# bio_dnt_main.net
KiCad netlist of a schematic drawn in Altium Designer
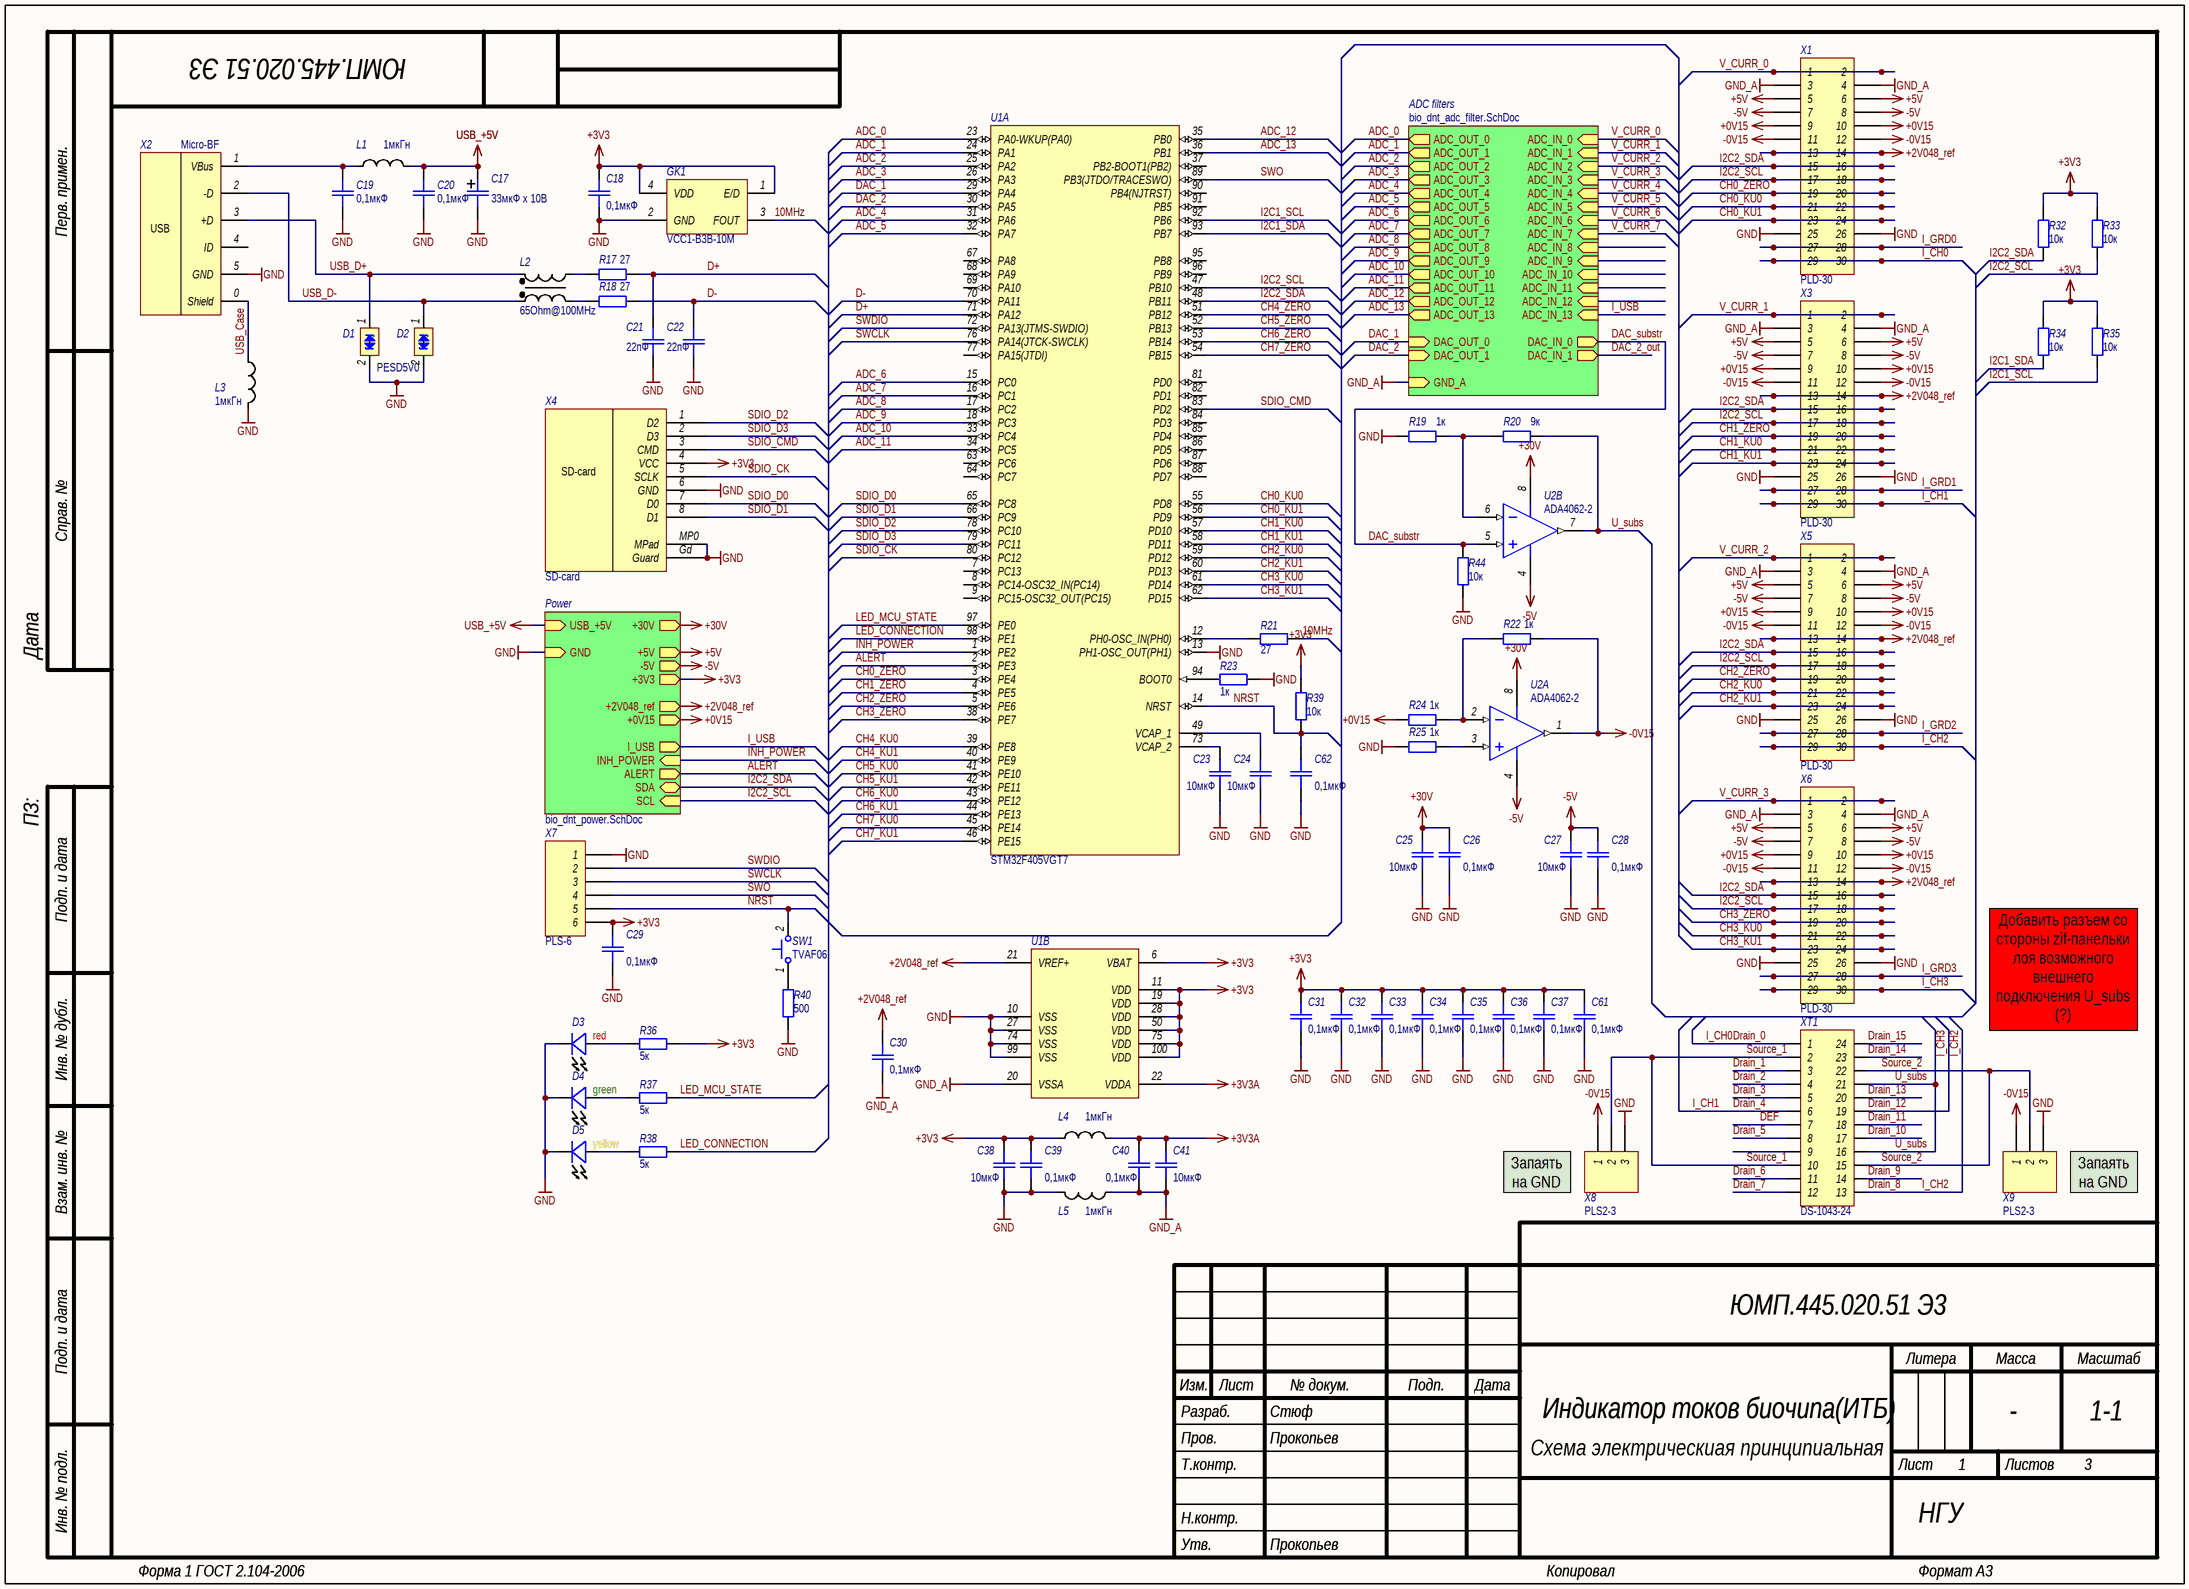
[diagram p0: bio_dnt_main.SchDoc]

(export (version "E")
  (design (tool "Eeschema 10.0.6"))
  (components
    (comp (ref "C17")
      (value "33мкФ х 10В")
      (footprint "C_SMD_size_C")
      (description "Поляризованный конеднсатор для поверхностного монтажа")
      (libsource (lib "my_passive") (part "C_pol_smd"))
    )
    (comp (ref "C18")
      (value "0,1мкФ")
      (footprint "CR-0805")
      (description "Конденсатор для поверхностного монтажа")
      (libsource (lib "my_passive") (part "C_smd"))
    )
    (comp (ref "C19")
      (value "0,1мкФ")
      (footprint "CR-0805")
      (description "Конденсатор для поверхностного монтажа")
      (libsource (lib "my_passive") (part "C_smd"))
    )
    (comp (ref "C20")
      (value "0,1мкФ")
      (footprint "CR-0805")
      (description "Конденсатор для поверхностного монтажа")
      (libsource (lib "my_passive") (part "C_smd"))
    )
    (comp (ref "C21")
      (value "22пФ")
      (footprint "CR-0805")
      (description "Конденсатор для поверхностного монтажа")
      (libsource (lib "my_passive") (part "C_smd"))
    )
    (comp (ref "C22")
      (value "22пФ")
      (footprint "CR-0805")
      (description "Конденсатор для поверхностного монтажа")
      (libsource (lib "my_passive") (part "C_smd"))
    )
    (comp (ref "C23")
      (value "10мкФ")
      (footprint "CR-0805")
      (description "Конденсатор для поверхностного монтажа")
      (libsource (lib "my_passive") (part "C_smd"))
    )
    (comp (ref "C24")
      (value "10мкФ")
      (footprint "CR-0805")
      (description "Конденсатор для поверхностного монтажа")
      (libsource (lib "my_passive") (part "C_smd"))
    )
    (comp (ref "C25")
      (value "10мкФ")
      (footprint "CR-0805")
      (description "Конденсатор для поверхностного монтажа")
      (libsource (lib "my_passive") (part "C_smd"))
    )
    (comp (ref "C26")
      (value "0,1мкФ")
      (footprint "CR-0805")
      (description "Конденсатор для поверхностного монтажа")
      (libsource (lib "my_passive") (part "C_smd"))
    )
    (comp (ref "C27")
      (value "10мкФ")
      (footprint "CR-0805")
      (description "Конденсатор для поверхностного монтажа")
      (libsource (lib "my_passive") (part "C_smd"))
    )
    (comp (ref "C28")
      (value "0,1мкФ")
      (footprint "CR-0805")
      (description "Конденсатор для поверхностного монтажа")
      (libsource (lib "my_passive") (part "C_smd"))
    )
    (comp (ref "C29")
      (value "0,1мкФ")
      (footprint "CR-0805")
      (description "Конденсатор для поверхностного монтажа")
      (libsource (lib "my_passive") (part "C_smd"))
    )
    (comp (ref "C30")
      (value "0,1мкФ")
      (footprint "CR-0805")
      (description "Конденсатор для поверхностного монтажа")
      (libsource (lib "my_passive") (part "C_smd"))
    )
    (comp (ref "C31")
      (value "0,1мкФ")
      (footprint "CR-0805")
      (description "Конденсатор для поверхностного монтажа")
      (libsource (lib "my_passive") (part "C_smd"))
    )
    (comp (ref "C32")
      (value "0,1мкФ")
      (footprint "CR-0805")
      (description "Конденсатор для поверхностного монтажа")
      (libsource (lib "my_passive") (part "C_smd"))
    )
    (comp (ref "C33")
      (value "0,1мкФ")
      (footprint "CR-0805")
      (description "Конденсатор для поверхностного монтажа")
      (libsource (lib "my_passive") (part "C_smd"))
    )
    (comp (ref "C34")
      (value "0,1мкФ")
      (footprint "CR-0805")
      (description "Конденсатор для поверхностного монтажа")
      (libsource (lib "my_passive") (part "C_smd"))
    )
    (comp (ref "C35")
      (value "0,1мкФ")
      (footprint "CR-0805")
      (description "Конденсатор для поверхностного монтажа")
      (libsource (lib "my_passive") (part "C_smd"))
    )
    (comp (ref "C36")
      (value "0,1мкФ")
      (footprint "CR-0805")
      (description "Конденсатор для поверхностного монтажа")
      (libsource (lib "my_passive") (part "C_smd"))
    )
    (comp (ref "C37")
      (value "0,1мкФ")
      (footprint "CR-0805")
      (description "Конденсатор для поверхностного монтажа")
      (libsource (lib "my_passive") (part "C_smd"))
    )
    (comp (ref "C38")
      (value "10мкФ")
      (footprint "CR-0805")
      (description "Конденсатор для поверхностного монтажа")
      (libsource (lib "my_passive") (part "C_smd"))
    )
    (comp (ref "C39")
      (value "0,1мкФ")
      (footprint "CR-0805")
      (description "Конденсатор для поверхностного монтажа")
      (libsource (lib "my_passive") (part "C_smd"))
    )
    (comp (ref "C40")
      (value "0,1мкФ")
      (footprint "CR-0805")
      (description "Конденсатор для поверхностного монтажа")
      (libsource (lib "my_passive") (part "C_smd"))
    )
    (comp (ref "C41")
      (value "10мкФ")
      (footprint "CR-0805")
      (description "Конденсатор для поверхностного монтажа")
      (libsource (lib "my_passive") (part "C_smd"))
    )
    (comp (ref "C61")
      (value "0,1мкФ")
      (footprint "CR-0805")
      (description "Конденсатор для поверхностного монтажа")
      (libsource (lib "my_passive") (part "C_smd"))
    )
    (comp (ref "C62")
      (value "0,1мкФ")
      (footprint "CR-0805")
      (description "Конденсатор для поверхностного монтажа")
      (libsource (lib "my_passive") (part "C_smd"))
    )
    (comp (ref "D1")
      (value "PESD5V0")
      (footprint "SOD-323")
      (description "Low capacitance bidirectional ESD protection diodes")
      (libsource (lib "my_semicond") (part "PESD5V0S"))
    )
    (comp (ref "D2")
      (value "PESD5V0")
      (footprint "SOD-323")
      (description "Low capacitance bidirectional ESD protection diodes")
      (libsource (lib "my_semicond") (part "PESD5V0S"))
    )
    (comp (ref "D3")
      (value "red")
      (footprint "LED-0805")
      (fields (field (name "Comment") "LED"))
      (libsource (lib "my_semicond") (part "LED"))
    )
    (comp (ref "D4")
      (value "green")
      (footprint "LED-0805")
      (fields (field (name "Comment") "LED"))
      (libsource (lib "my_semicond") (part "LED"))
    )
    (comp (ref "D5")
      (value "yellow")
      (footprint "LED-0805")
      (fields (field (name "Comment") "LED"))
      (libsource (lib "my_semicond") (part "LED"))
    )
    (comp (ref "GK1")
      (value "VCC1")
      (footprint "5x7 Crystall Oscillatior")
      (fields (field (name "НАИМЕНОВАНИЕ") "VCC1-B3B-10M"))
      (libsource (lib "my_integrated_circuit") (part "Crystall Oscillator"))
    )
    (comp (ref "L1")
      (value "1мкГн")
      (footprint "CR-1206")
      (description "Индуктивность для поверхностнгого монтажа")
      (libsource (lib "my_passive") (part "L_smd"))
    )
    (comp (ref "L2")
      (value "65Ohm@100MHz")
      (footprint "ACM2012")
      (description "USB common mode filter")
      (libsource (lib "my_passive") (part "ACM2012_USB_CM_FILTER"))
    )
    (comp (ref "L3")
      (value "1мкГн")
      (footprint "CR-1206-0805")
      (description "Индуктивность для поверхностнгого монтажа")
      (libsource (lib "my_passive") (part "L_smd"))
    )
    (comp (ref "L4")
      (value "1мкГн")
      (footprint "CR-1206-0805")
      (description "Индуктивность для поверхностнгого монтажа")
      (libsource (lib "my_passive") (part "L_smd"))
    )
    (comp (ref "L5")
      (value "1мкГн")
      (footprint "CR-1206-0805")
      (description "Индуктивность для поверхностнгого монтажа")
      (libsource (lib "my_passive") (part "L_smd"))
    )
    (comp (ref "R17")
      (value "27")
      (footprint "CR-0805")
      (description "Резистор для поверхностного монтажа")
      (libsource (lib "") (part "R_smd_1"))
    )
    (comp (ref "R18")
      (value "27")
      (footprint "CR-0805")
      (description "Резистор для поверхностного монтажа")
      (libsource (lib "") (part "R_smd_1"))
    )
    (comp (ref "R19")
      (value "1к")
      (footprint "CR-0805")
      (description "Резистор для поверхностного монтажа")
      (libsource (lib "") (part "R_smd_1"))
    )
    (comp (ref "R20")
      (value "9к")
      (footprint "CR-0805")
      (description "Резистор для поверхностного монтажа")
      (libsource (lib "") (part "R_smd_1"))
    )
    (comp (ref "R21")
      (value "27")
      (footprint "CR-0805")
      (description "Резистор для поверхностного монтажа")
      (libsource (lib "") (part "R_smd_2"))
    )
    (comp (ref "R22")
      (value "1к")
      (footprint "CR-0805")
      (description "Резистор для поверхностного монтажа")
      (libsource (lib "") (part "R_smd_1"))
    )
    (comp (ref "R23")
      (value "1к")
      (footprint "CR-0805")
      (description "Резистор для поверхностного монтажа")
      (libsource (lib "") (part "R_smd_1"))
    )
    (comp (ref "R24")
      (value "1к")
      (footprint "CR-0805")
      (description "Резистор для поверхностного монтажа")
      (libsource (lib "") (part "R_smd_1"))
    )
    (comp (ref "R25")
      (value "1к")
      (footprint "CR-0805")
      (description "Резистор для поверхностного монтажа")
      (libsource (lib "") (part "R_smd_1"))
    )
    (comp (ref "R32")
      (value "10к")
      (footprint "CR-0805")
      (description "Резистор для поверхностного монтажа")
      (libsource (lib "my_passive") (part "R_smd"))
    )
    (comp (ref "R33")
      (value "10к")
      (footprint "CR-0805")
      (description "Резистор для поверхностного монтажа")
      (libsource (lib "my_passive") (part "R_smd"))
    )
    (comp (ref "R34")
      (value "10к")
      (footprint "CR-0805")
      (description "Резистор для поверхностного монтажа")
      (libsource (lib "my_passive") (part "R_smd"))
    )
    (comp (ref "R35")
      (value "10к")
      (footprint "CR-0805")
      (description "Резистор для поверхностного монтажа")
      (libsource (lib "my_passive") (part "R_smd"))
    )
    (comp (ref "R36")
      (value "5к")
      (footprint "CR-0805")
      (description "Резистор для поверхностного монтажа")
      (libsource (lib "") (part "R_smd_1"))
    )
    (comp (ref "R37")
      (value "5к")
      (footprint "CR-0805")
      (description "Резистор для поверхностного монтажа")
      (libsource (lib "") (part "R_smd_1"))
    )
    (comp (ref "R38")
      (value "5к")
      (footprint "CR-0805")
      (description "Резистор для поверхностного монтажа")
      (libsource (lib "") (part "R_smd_1"))
    )
    (comp (ref "R39")
      (value "10к")
      (footprint "CR-0805")
      (description "Резистор для поверхностного монтажа")
      (libsource (lib "my_passive") (part "R_smd"))
    )
    (comp (ref "R40")
      (value "500")
      (footprint "CR-0805")
      (description "Резистор для поверхностного монтажа")
      (libsource (lib "") (part "R_smd_3"))
    )
    (comp (ref "R44")
      (value "10к")
      (footprint "CR-0805")
      (description "Резистор для поверхностного монтажа")
      (libsource (lib "my_passive") (part "R_smd"))
    )
    (comp (ref "SW1")
      (value "Push button")
      (footprint "TVAF06")
      (fields (field (name "НАИМЕНОВАНИЕ") "TVAF06"))
      (libsource (lib "my_passive") (part "Push_Button"))
    )
    (comp (ref "U1")
      (value "STM32F405VGT7")
      (footprint "LQFP100")
      (fields
        (field (name "MANUFACTURER") "STMicroelectronics")
        (field (name "НАИМЕНОВАНИЕ") "STM32F405VGT7")
      )
      (libsource (lib "") (part "STM32F405VGT_1"))
    )
    (comp (ref "U2")
      (value "ADA4062-2ARZ")
      (footprint "SOIC-8")
      (fields
        (field (name "GENERIC PART NUMBER") "ADA4062-2")
        (field (name "MANUFACTURER") "Analog Devices")
        (field (name "НАИМЕНОВАНИЕ") "ADA4062-2")
      )
      (libsource (lib "my_op_amplifier") (part "ADA4062-2"))
    )
    (comp (ref "X1")
      (value "HDR2X15")
      (footprint "HDR2X15")
      (description "Header, 15-Pin, Dual row")
      (fields (field (name "НАИМЕНОВАНИЕ") "PLD-30") (field (name "PUBLISHER") "Altium Limited"))
      (libsource (lib "my_connector") (part "HDR2X15"))
    )
    (comp (ref "X2")
      (value "mico-BF")
      (footprint "USB Micro-BF")
      (description "USB mico-BF")
      (fields (field (name "НАИМЕНОВАНИЕ") "Micro-BF"))
      (libsource (lib "my_connector") (part "MicroUSB"))
    )
    (comp (ref "X3")
      (value "HDR2X15")
      (footprint "HDR2X15")
      (description "Header, 15-Pin, Dual row")
      (fields (field (name "НАИМЕНОВАНИЕ") "PLD-30") (field (name "PUBLISHER") "Altium Limited"))
      (libsource (lib "my_connector") (part "HDR2X15"))
    )
    (comp (ref "X4")
      (value "SD-card")
      (footprint "SD-card holder")
      (description "SD-card holder")
      (fields (field (name "НАИМЕНОВАНИЕ") "SD-card"))
      (libsource (lib "my_connector") (part "SD-card holder"))
    )
    (comp (ref "X5")
      (value "HDR2X15")
      (footprint "HDR2X15")
      (description "Header, 15-Pin, Dual row")
      (fields (field (name "НАИМЕНОВАНИЕ") "PLD-30") (field (name "PUBLISHER") "Altium Limited"))
      (libsource (lib "my_connector") (part "HDR2X15"))
    )
    (comp (ref "X6")
      (value "HDR2X15")
      (footprint "HDR2X15")
      (description "Header, 15-Pin, Dual row")
      (fields (field (name "НАИМЕНОВАНИЕ") "PLD-30") (field (name "PUBLISHER") "Altium Limited"))
      (libsource (lib "my_connector") (part "HDR2X15"))
    )
    (comp (ref "X7")
      (value "Header 6")
      (footprint "HDR1X6")
      (description "Header, 6-Pin")
      (fields (field (name "НАИМЕНОВАНИЕ") "PLS-6") (field (name "PUBLISHER") "Altium Limited"))
      (libsource (lib "Miscellaneous Connectors") (part "Header 6"))
    )
    (comp (ref "X8")
      (value "MHDR1X3")
      (footprint "MHDR1X3")
      (description "Header, 3-Pin")
      (fields (field (name "НАИМЕНОВАНИЕ") "PLS2-3") (field (name "PUBLISHER") "Altium Limited"))
      (libsource (lib "my_connector") (part "MHDR1X3"))
    )
    (comp (ref "X9")
      (value "MHDR1X3")
      (footprint "MHDR1X3")
      (description "Header, 3-Pin")
      (fields (field (name "НАИМЕНОВАНИЕ") "PLS2-3") (field (name "PUBLISHER") "Altium Limited"))
      (libsource (lib "my_connector") (part "MHDR1X3"))
    )
    (comp (ref "XT1")
      (value "DS-1043-24")
      (footprint "DS-1043-24")
      (description "DIP-24 Zero Insertion Force (ZIF) socket")
      (fields (field (name "НАИМЕНОВАНИЕ") "DS-1043-24"))
      (libsource (lib "my_connector") (part "DS-1043-24"))
    )
  )
  (nets
    (net (code "1") (name "+0V15") (class "Default")
      (node (ref "R24") (pin "2") (pinfunction "2_2") (pintype "passive"))
      (node (ref "X1") (pin "10") (pinfunction "10_10") (pintype "passive"))
      (node (ref "X1") (pin "9") (pinfunction "9_9") (pintype "passive"))
      (node (ref "X3") (pin "10") (pinfunction "10_10") (pintype "passive"))
      (node (ref "X3") (pin "9") (pinfunction "9_9") (pintype "passive"))
      (node (ref "X5") (pin "10") (pinfunction "10_10") (pintype "passive"))
      (node (ref "X5") (pin "9") (pinfunction "9_9") (pintype "passive"))
      (node (ref "X6") (pin "10") (pinfunction "10_10") (pintype "passive"))
      (node (ref "X6") (pin "9") (pinfunction "9_9") (pintype "passive"))
    )
    (net (code "2") (name "+2V048_ref") (class "Default")
      (node (ref "C30") (pin "2") (pinfunction "2_2") (pintype "passive"))
      (node (ref "U1") (pin "21") (pinfunction "VREF+_21") (pintype "power_in"))
      (node (ref "X1") (pin "13") (pinfunction "13_13") (pintype "passive"))
      (node (ref "X1") (pin "14") (pinfunction "14_14") (pintype "passive"))
      (node (ref "X3") (pin "13") (pinfunction "13_13") (pintype "passive"))
      (node (ref "X3") (pin "14") (pinfunction "14_14") (pintype "passive"))
      (node (ref "X5") (pin "13") (pinfunction "13_13") (pintype "passive"))
      (node (ref "X5") (pin "14") (pinfunction "14_14") (pintype "passive"))
      (node (ref "X6") (pin "13") (pinfunction "13_13") (pintype "passive"))
      (node (ref "X6") (pin "14") (pinfunction "14_14") (pintype "passive"))
    )
    (net (code "3") (name "+3V3") (class "Default")
      (node (ref "C18") (pin "2") (pinfunction "2_2") (pintype "passive"))
      (node (ref "C29") (pin "2") (pinfunction "2_2") (pintype "passive"))
      (node (ref "C31") (pin "2") (pinfunction "2_2") (pintype "passive"))
      (node (ref "C32") (pin "2") (pinfunction "2_2") (pintype "passive"))
      (node (ref "C33") (pin "2") (pinfunction "2_2") (pintype "passive"))
      (node (ref "C34") (pin "2") (pinfunction "2_2") (pintype "passive"))
      (node (ref "C35") (pin "2") (pinfunction "2_2") (pintype "passive"))
      (node (ref "C36") (pin "2") (pinfunction "2_2") (pintype "passive"))
      (node (ref "C37") (pin "2") (pinfunction "2_2") (pintype "passive"))
      (node (ref "C38") (pin "2") (pinfunction "2_2") (pintype "passive"))
      (node (ref "C39") (pin "2") (pinfunction "2_2") (pintype "passive"))
      (node (ref "C61") (pin "2") (pinfunction "2_2") (pintype "passive"))
      (node (ref "GK1") (pin "1") (pinfunction "E/D_1") (pintype "passive"))
      (node (ref "GK1") (pin "4") (pinfunction "VDD_4") (pintype "passive"))
      (node (ref "L4") (pin "1") (pinfunction "1_1") (pintype "passive"))
      (node (ref "R32") (pin "1") (pinfunction "1_1") (pintype "passive"))
      (node (ref "R33") (pin "1") (pinfunction "1_1") (pintype "passive"))
      (node (ref "R34") (pin "1") (pinfunction "1_1") (pintype "passive"))
      (node (ref "R35") (pin "1") (pinfunction "1_1") (pintype "passive"))
      (node (ref "R36") (pin "1") (pinfunction "1_1") (pintype "passive"))
      (node (ref "R39") (pin "1") (pinfunction "1_1") (pintype "passive"))
      (node (ref "U1") (pin "100") (pinfunction "VDD_100") (pintype "power_in"))
      (node (ref "U1") (pin "11") (pinfunction "VDD_11") (pintype "power_in"))
      (node (ref "U1") (pin "19") (pinfunction "VDD_19") (pintype "power_in"))
      (node (ref "U1") (pin "28") (pinfunction "VDD_28") (pintype "power_in"))
      (node (ref "U1") (pin "50") (pinfunction "VDD_50") (pintype "power_in"))
      (node (ref "U1") (pin "6") (pinfunction "VBAT_6") (pintype "power_in"))
      (node (ref "U1") (pin "75") (pinfunction "VDD_75") (pintype "power_in"))
      (node (ref "X4") (pin "4") (pinfunction "VCC_4") (pintype "passive"))
      (node (ref "X7") (pin "6") (pinfunction "6_6") (pintype "passive"))
    )
    (net (code "4") (name "+3V3A") (class "Default")
      (node (ref "C40") (pin "2") (pinfunction "2_2") (pintype "passive"))
      (node (ref "C41") (pin "2") (pinfunction "2_2") (pintype "passive"))
      (node (ref "L4") (pin "2") (pinfunction "2_2") (pintype "passive"))
      (node (ref "U1") (pin "22") (pinfunction "VDDA_22") (pintype "power_in"))
    )
    (net (code "5") (name "+5V") (class "Default")
      (node (ref "X1") (pin "5") (pinfunction "5_5") (pintype "passive"))
      (node (ref "X1") (pin "6") (pinfunction "6_6") (pintype "passive"))
      (node (ref "X3") (pin "5") (pinfunction "5_5") (pintype "passive"))
      (node (ref "X3") (pin "6") (pinfunction "6_6") (pintype "passive"))
      (node (ref "X5") (pin "5") (pinfunction "5_5") (pintype "passive"))
      (node (ref "X5") (pin "6") (pinfunction "6_6") (pintype "passive"))
      (node (ref "X6") (pin "5") (pinfunction "5_5") (pintype "passive"))
      (node (ref "X6") (pin "6") (pinfunction "6_6") (pintype "passive"))
    )
    (net (code "6") (name "+30V") (class "Default")
      (node (ref "C25") (pin "2") (pinfunction "2_2") (pintype "passive"))
      (node (ref "C26") (pin "2") (pinfunction "2_2") (pintype "passive"))
      (node (ref "U2") (pin "8") (pinfunction "+V_8") (pintype "power_in"))
    )
    (net (code "7") (name "-0V15") (class "Default")
      (node (ref "R22") (pin "1") (pinfunction "1_1") (pintype "passive"))
      (node (ref "U2") (pin "1") (pinfunction "OUT_A_1") (pintype "output"))
      (node (ref "X1") (pin "11") (pinfunction "11_11") (pintype "passive"))
      (node (ref "X1") (pin "12") (pinfunction "12_12") (pintype "passive"))
      (node (ref "X3") (pin "11") (pinfunction "11_11") (pintype "passive"))
      (node (ref "X3") (pin "12") (pinfunction "12_12") (pintype "passive"))
      (node (ref "X5") (pin "11") (pinfunction "11_11") (pintype "passive"))
      (node (ref "X5") (pin "12") (pinfunction "12_12") (pintype "passive"))
      (node (ref "X6") (pin "11") (pinfunction "11_11") (pintype "passive"))
      (node (ref "X6") (pin "12") (pinfunction "12_12") (pintype "passive"))
      (node (ref "X8") (pin "1") (pinfunction "1_1") (pintype "passive"))
      (node (ref "X9") (pin "1") (pinfunction "1_1") (pintype "passive"))
    )
    (net (code "8") (name "-5V") (class "Default")
      (node (ref "C27") (pin "2") (pinfunction "2_2") (pintype "passive"))
      (node (ref "C28") (pin "2") (pinfunction "2_2") (pintype "passive"))
      (node (ref "U2") (pin "4") (pinfunction "-V_4") (pintype "power_in"))
      (node (ref "X1") (pin "7") (pinfunction "7_7") (pintype "passive"))
      (node (ref "X1") (pin "8") (pinfunction "8_8") (pintype "passive"))
      (node (ref "X3") (pin "7") (pinfunction "7_7") (pintype "passive"))
      (node (ref "X3") (pin "8") (pinfunction "8_8") (pintype "passive"))
      (node (ref "X5") (pin "7") (pinfunction "7_7") (pintype "passive"))
      (node (ref "X5") (pin "8") (pinfunction "8_8") (pintype "passive"))
      (node (ref "X6") (pin "7") (pinfunction "7_7") (pintype "passive"))
      (node (ref "X6") (pin "8") (pinfunction "8_8") (pintype "passive"))
    )
    (net (code "9") (name "/10MHz") (class "Default")
      (node (ref "GK1") (pin "3") (pinfunction "FOUT_3") (pintype "passive"))
      (node (ref "R21") (pin "2") (pinfunction "2_2") (pintype "passive"))
    )
    (net (code "10") (name "/ADC_0") (class "Default")
      (node (ref "U1") (pin "23") (pinfunction "PA0-WKUP(PA0)_23") (pintype "bidirectional"))
    )
    (net (code "11") (name "/ADC_1") (class "Default")
      (node (ref "U1") (pin "24") (pinfunction "PA1_24") (pintype "bidirectional"))
    )
    (net (code "12") (name "/ADC_2") (class "Default")
      (node (ref "U1") (pin "25") (pinfunction "PA2_25") (pintype "bidirectional"))
    )
    (net (code "13") (name "/ADC_3") (class "Default")
      (node (ref "U1") (pin "26") (pinfunction "PA3_26") (pintype "bidirectional"))
    )
    (net (code "14") (name "/ADC_4") (class "Default")
      (node (ref "U1") (pin "31") (pinfunction "PA6_31") (pintype "bidirectional"))
    )
    (net (code "15") (name "/ADC_5") (class "Default")
      (node (ref "U1") (pin "32") (pinfunction "PA7_32") (pintype "bidirectional"))
    )
    (net (code "16") (name "/ADC_6") (class "Default")
      (node (ref "U1") (pin "15") (pinfunction "PC0_15") (pintype "bidirectional"))
    )
    (net (code "17") (name "/ADC_7") (class "Default")
      (node (ref "U1") (pin "16") (pinfunction "PC1_16") (pintype "bidirectional"))
    )
    (net (code "18") (name "/ADC_8") (class "Default")
      (node (ref "U1") (pin "17") (pinfunction "PC2_17") (pintype "bidirectional"))
    )
    (net (code "19") (name "/ADC_9") (class "Default")
      (node (ref "U1") (pin "18") (pinfunction "PC3_18") (pintype "bidirectional"))
    )
    (net (code "20") (name "/ADC_10") (class "Default")
      (node (ref "U1") (pin "33") (pinfunction "PC4_33") (pintype "bidirectional"))
    )
    (net (code "21") (name "/ADC_11") (class "Default")
      (node (ref "U1") (pin "34") (pinfunction "PC5_34") (pintype "bidirectional"))
    )
    (net (code "22") (name "/ADC_12") (class "Default")
      (node (ref "U1") (pin "35") (pinfunction "PB0_35") (pintype "bidirectional"))
    )
    (net (code "23") (name "/ADC_13") (class "Default")
      (node (ref "U1") (pin "36") (pinfunction "PB1_36") (pintype "bidirectional"))
    )
    (net (code "29") (name "/ALERT") (class "Default")
      (node (ref "U1") (pin "2") (pinfunction "PE3_2") (pintype "bidirectional"))
    )
    (net (code "30") (name "/CH0_KU0") (class "Default")
      (node (ref "U1") (pin "55") (pinfunction "PD8_55") (pintype "bidirectional"))
      (node (ref "X1") (pin "21") (pinfunction "21_21") (pintype "passive"))
      (node (ref "X1") (pin "22") (pinfunction "22_22") (pintype "passive"))
    )
    (net (code "31") (name "/CH0_KU1") (class "Default")
      (node (ref "U1") (pin "56") (pinfunction "PD9_56") (pintype "bidirectional"))
      (node (ref "X1") (pin "23") (pinfunction "23_23") (pintype "passive"))
      (node (ref "X1") (pin "24") (pinfunction "24_24") (pintype "passive"))
    )
    (net (code "32") (name "/CH0_ZERO") (class "Default")
      (node (ref "U1") (pin "3") (pinfunction "PE4_3") (pintype "bidirectional"))
      (node (ref "X1") (pin "19") (pinfunction "19_19") (pintype "passive"))
      (node (ref "X1") (pin "20") (pinfunction "20_20") (pintype "passive"))
    )
    (net (code "33") (name "/CH1_KU0") (class "Default")
      (node (ref "U1") (pin "57") (pinfunction "PD10_57") (pintype "bidirectional"))
      (node (ref "X3") (pin "21") (pinfunction "21_21") (pintype "passive"))
      (node (ref "X3") (pin "22") (pinfunction "22_22") (pintype "passive"))
    )
    (net (code "34") (name "/CH1_KU1") (class "Default")
      (node (ref "U1") (pin "58") (pinfunction "PD11_58") (pintype "bidirectional"))
      (node (ref "X3") (pin "23") (pinfunction "23_23") (pintype "passive"))
      (node (ref "X3") (pin "24") (pinfunction "24_24") (pintype "passive"))
    )
    (net (code "35") (name "/CH1_ZERO") (class "Default")
      (node (ref "U1") (pin "4") (pinfunction "PE5_4") (pintype "bidirectional"))
      (node (ref "X3") (pin "19") (pinfunction "19_19") (pintype "passive"))
      (node (ref "X3") (pin "20") (pinfunction "20_20") (pintype "passive"))
    )
    (net (code "36") (name "/CH2_KU0") (class "Default")
      (node (ref "U1") (pin "59") (pinfunction "PD12_59") (pintype "bidirectional"))
      (node (ref "X5") (pin "21") (pinfunction "21_21") (pintype "passive"))
      (node (ref "X5") (pin "22") (pinfunction "22_22") (pintype "passive"))
    )
    (net (code "37") (name "/CH2_KU1") (class "Default")
      (node (ref "U1") (pin "60") (pinfunction "PD13_60") (pintype "bidirectional"))
      (node (ref "X5") (pin "23") (pinfunction "23_23") (pintype "passive"))
      (node (ref "X5") (pin "24") (pinfunction "24_24") (pintype "passive"))
    )
    (net (code "38") (name "/CH2_ZERO") (class "Default")
      (node (ref "U1") (pin "5") (pinfunction "PE6_5") (pintype "bidirectional"))
      (node (ref "X5") (pin "19") (pinfunction "19_19") (pintype "passive"))
      (node (ref "X5") (pin "20") (pinfunction "20_20") (pintype "passive"))
    )
    (net (code "39") (name "/CH3_KU0") (class "Default")
      (node (ref "U1") (pin "61") (pinfunction "PD14_61") (pintype "bidirectional"))
      (node (ref "X6") (pin "21") (pinfunction "21_21") (pintype "passive"))
      (node (ref "X6") (pin "22") (pinfunction "22_22") (pintype "passive"))
    )
    (net (code "40") (name "/CH3_KU1") (class "Default")
      (node (ref "U1") (pin "62") (pinfunction "PD15_62") (pintype "bidirectional"))
      (node (ref "X6") (pin "23") (pinfunction "23_23") (pintype "passive"))
      (node (ref "X6") (pin "24") (pinfunction "24_24") (pintype "passive"))
    )
    (net (code "41") (name "/CH3_ZERO") (class "Default")
      (node (ref "U1") (pin "38") (pinfunction "PE7_38") (pintype "bidirectional"))
      (node (ref "X6") (pin "19") (pinfunction "19_19") (pintype "passive"))
      (node (ref "X6") (pin "20") (pinfunction "20_20") (pintype "passive"))
    )
    (net (code "42") (name "/CH4_KU0") (class "Default")
      (node (ref "U1") (pin "39") (pinfunction "PE8_39") (pintype "bidirectional"))
    )
    (net (code "43") (name "/CH4_KU1") (class "Default")
      (node (ref "U1") (pin "40") (pinfunction "PE9_40") (pintype "bidirectional"))
    )
    (net (code "44") (name "/CH4_ZERO") (class "Default")
      (node (ref "U1") (pin "51") (pinfunction "PB12_51") (pintype "bidirectional"))
    )
    (net (code "45") (name "/CH5_KU0") (class "Default")
      (node (ref "U1") (pin "41") (pinfunction "PE10_41") (pintype "bidirectional"))
    )
    (net (code "46") (name "/CH5_KU1") (class "Default")
      (node (ref "U1") (pin "42") (pinfunction "PE11_42") (pintype "bidirectional"))
    )
    (net (code "47") (name "/CH5_ZERO") (class "Default")
      (node (ref "U1") (pin "52") (pinfunction "PB13_52") (pintype "bidirectional"))
    )
    (net (code "48") (name "/CH6_KU0") (class "Default")
      (node (ref "U1") (pin "43") (pinfunction "PE12_43") (pintype "bidirectional"))
    )
    (net (code "49") (name "/CH6_KU1") (class "Default")
      (node (ref "U1") (pin "44") (pinfunction "PE13_44") (pintype "bidirectional"))
    )
    (net (code "50") (name "/CH6_ZERO") (class "Default")
      (node (ref "U1") (pin "53") (pinfunction "PB14_53") (pintype "bidirectional"))
    )
    (net (code "51") (name "/CH7_KU0") (class "Default")
      (node (ref "U1") (pin "45") (pinfunction "PE14_45") (pintype "bidirectional"))
    )
    (net (code "52") (name "/CH7_KU1") (class "Default")
      (node (ref "U1") (pin "46") (pinfunction "PE15_46") (pintype "bidirectional"))
    )
    (net (code "53") (name "/CH7_ZERO") (class "Default")
      (node (ref "U1") (pin "54") (pinfunction "PB15_54") (pintype "bidirectional"))
    )
    (net (code "54") (name "/D+") (class "Default")
      (node (ref "C21") (pin "2") (pinfunction "2_2") (pintype "passive"))
      (node (ref "R17") (pin "1") (pinfunction "1_1") (pintype "passive"))
      (node (ref "U1") (pin "71") (pinfunction "PA12_71") (pintype "bidirectional"))
    )
    (net (code "55") (name "/D-") (class "Default")
      (node (ref "C22") (pin "2") (pinfunction "2_2") (pintype "passive"))
      (node (ref "R18") (pin "1") (pinfunction "1_1") (pintype "passive"))
      (node (ref "U1") (pin "70") (pinfunction "PA11_70") (pintype "bidirectional"))
    )
    (net (code "56") (name "/DAC_1") (class "Default")
      (node (ref "U1") (pin "29") (pinfunction "PA4_29") (pintype "bidirectional"))
    )
    (net (code "57") (name "/DAC_2") (class "Default")
      (node (ref "U1") (pin "30") (pinfunction "PA5_30") (pintype "bidirectional"))
    )
    (net (code "59") (name "/DAC_substr") (class "Default")
      (node (ref "R44") (pin "1") (pinfunction "1_1") (pintype "passive"))
      (node (ref "U2") (pin "5") (pinfunction "+IN_B_5") (pintype "input"))
    )
    (net (code "60") (name "/DEF") (class "Default")
      (node (ref "XT1") (pin "7") (pinfunction "7_7") (pintype "passive"))
    )
    (net (code "61") (name "/Drain_0") (class "Default")
      (node (ref "X1") (pin "29") (pinfunction "29_29") (pintype "passive"))
      (node (ref "X1") (pin "30") (pinfunction "30_30") (pintype "passive"))
      (node (ref "XT1") (pin "1") (pinfunction "1_1") (pintype "passive"))
    )
    (net (code "62") (name "/Drain_1") (class "Default")
      (node (ref "XT1") (pin "3") (pinfunction "3_3") (pintype "passive"))
    )
    (net (code "63") (name "/Drain_2") (class "Default")
      (node (ref "XT1") (pin "4") (pinfunction "4_4") (pintype "passive"))
    )
    (net (code "64") (name "/Drain_3") (class "Default")
      (node (ref "XT1") (pin "5") (pinfunction "5_5") (pintype "passive"))
    )
    (net (code "65") (name "/Drain_4") (class "Default")
      (node (ref "X3") (pin "29") (pinfunction "29_29") (pintype "passive"))
      (node (ref "X3") (pin "30") (pinfunction "30_30") (pintype "passive"))
      (node (ref "XT1") (pin "6") (pinfunction "6_6") (pintype "passive"))
    )
    (net (code "66") (name "/Drain_5") (class "Default")
      (node (ref "XT1") (pin "8") (pinfunction "8_8") (pintype "passive"))
    )
    (net (code "67") (name "/Drain_6") (class "Default")
      (node (ref "XT1") (pin "11") (pinfunction "11_11") (pintype "passive"))
    )
    (net (code "68") (name "/Drain_7") (class "Default")
      (node (ref "XT1") (pin "12") (pinfunction "12_12") (pintype "passive"))
    )
    (net (code "69") (name "/Drain_8") (class "Default")
      (node (ref "X5") (pin "29") (pinfunction "29_29") (pintype "passive"))
      (node (ref "X5") (pin "30") (pinfunction "30_30") (pintype "passive"))
      (node (ref "XT1") (pin "13") (pinfunction "13_13") (pintype "passive"))
    )
    (net (code "70") (name "/Drain_9") (class "Default")
      (node (ref "XT1") (pin "14") (pinfunction "14_14") (pintype "passive"))
    )
    (net (code "71") (name "/Drain_10") (class "Default")
      (node (ref "XT1") (pin "17") (pinfunction "17_17") (pintype "passive"))
    )
    (net (code "72") (name "/Drain_11") (class "Default")
      (node (ref "XT1") (pin "18") (pinfunction "18_18") (pintype "passive"))
    )
    (net (code "73") (name "/Drain_12") (class "Default")
      (node (ref "X6") (pin "29") (pinfunction "29_29") (pintype "passive"))
      (node (ref "X6") (pin "30") (pinfunction "30_30") (pintype "passive"))
      (node (ref "XT1") (pin "19") (pinfunction "19_19") (pintype "passive"))
    )
    (net (code "74") (name "/Drain_13") (class "Default")
      (node (ref "XT1") (pin "20") (pinfunction "20_20") (pintype "passive"))
    )
    (net (code "75") (name "/Drain_14") (class "Default")
      (node (ref "XT1") (pin "23") (pinfunction "23_23") (pintype "passive"))
    )
    (net (code "76") (name "/Drain_15") (class "Default")
      (node (ref "XT1") (pin "24") (pinfunction "24_24") (pintype "passive"))
    )
    (net (code "77") (name "/I2C1_SCL") (class "Default")
      (node (ref "R35") (pin "2") (pinfunction "2_2") (pintype "passive"))
      (node (ref "U1") (pin "92") (pinfunction "PB6_92") (pintype "bidirectional"))
    )
    (net (code "78") (name "/I2C1_SDA") (class "Default")
      (node (ref "R34") (pin "2") (pinfunction "2_2") (pintype "passive"))
      (node (ref "U1") (pin "93") (pinfunction "PB7_93") (pintype "bidirectional"))
    )
    (net (code "79") (name "/I2C2_SCL") (class "Default")
      (node (ref "R33") (pin "2") (pinfunction "2_2") (pintype "passive"))
      (node (ref "U1") (pin "47") (pinfunction "PB10_47") (pintype "bidirectional"))
      (node (ref "X1") (pin "17") (pinfunction "17_17") (pintype "passive"))
      (node (ref "X1") (pin "18") (pinfunction "18_18") (pintype "passive"))
      (node (ref "X3") (pin "17") (pinfunction "17_17") (pintype "passive"))
      (node (ref "X3") (pin "18") (pinfunction "18_18") (pintype "passive"))
      (node (ref "X5") (pin "17") (pinfunction "17_17") (pintype "passive"))
      (node (ref "X5") (pin "18") (pinfunction "18_18") (pintype "passive"))
      (node (ref "X6") (pin "17") (pinfunction "17_17") (pintype "passive"))
      (node (ref "X6") (pin "18") (pinfunction "18_18") (pintype "passive"))
    )
    (net (code "80") (name "/I2C2_SDA") (class "Default")
      (node (ref "R32") (pin "2") (pinfunction "2_2") (pintype "passive"))
      (node (ref "U1") (pin "48") (pinfunction "PB11_48") (pintype "bidirectional"))
      (node (ref "X1") (pin "15") (pinfunction "15_15") (pintype "passive"))
      (node (ref "X1") (pin "16") (pinfunction "16_16") (pintype "passive"))
      (node (ref "X3") (pin "15") (pinfunction "15_15") (pintype "passive"))
      (node (ref "X3") (pin "16") (pinfunction "16_16") (pintype "passive"))
      (node (ref "X5") (pin "15") (pinfunction "15_15") (pintype "passive"))
      (node (ref "X5") (pin "16") (pinfunction "16_16") (pintype "passive"))
      (node (ref "X6") (pin "15") (pinfunction "15_15") (pintype "passive"))
      (node (ref "X6") (pin "16") (pinfunction "16_16") (pintype "passive"))
    )
    (net (code "81") (name "/INH_POWER") (class "Default")
      (node (ref "U1") (pin "1") (pinfunction "PE2_1") (pintype "bidirectional"))
    )
    (net (code "82") (name "/I_GRD0") (class "Default")
      (node (ref "X1") (pin "27") (pinfunction "27_27") (pintype "passive"))
      (node (ref "X1") (pin "28") (pinfunction "28_28") (pintype "passive"))
    )
    (net (code "83") (name "/I_GRD1") (class "Default")
      (node (ref "X3") (pin "27") (pinfunction "27_27") (pintype "passive"))
      (node (ref "X3") (pin "28") (pinfunction "28_28") (pintype "passive"))
    )
    (net (code "84") (name "/I_GRD2") (class "Default")
      (node (ref "X5") (pin "27") (pinfunction "27_27") (pintype "passive"))
      (node (ref "X5") (pin "28") (pinfunction "28_28") (pintype "passive"))
    )
    (net (code "85") (name "/I_GRD3") (class "Default")
      (node (ref "X6") (pin "27") (pinfunction "27_27") (pintype "passive"))
      (node (ref "X6") (pin "28") (pinfunction "28_28") (pintype "passive"))
    )
    (net (code "87") (name "/LED_CONNECTION") (class "Default")
      (node (ref "R38") (pin "1") (pinfunction "1_1") (pintype "passive"))
      (node (ref "U1") (pin "98") (pinfunction "PE1_98") (pintype "bidirectional"))
    )
    (net (code "88") (name "/LED_MCU_STATE") (class "Default")
      (node (ref "R37") (pin "1") (pinfunction "1_1") (pintype "passive"))
      (node (ref "U1") (pin "97") (pinfunction "PE0_97") (pintype "bidirectional"))
    )
    (net (code "89") (name "/NRST") (class "Default")
      (node (ref "C62") (pin "2") (pinfunction "2_2") (pintype "passive"))
      (node (ref "R39") (pin "2") (pinfunction "2_2") (pintype "passive"))
      (node (ref "SW1") (pin "2") (pinfunction "2_2") (pintype "passive"))
      (node (ref "U1") (pin "14") (pinfunction "NRST_14") (pintype "bidirectional"))
      (node (ref "X7") (pin "5") (pinfunction "5_5") (pintype "passive"))
    )
    (net (code "90") (name "/SDIO_CK") (class "Default")
      (node (ref "U1") (pin "80") (pinfunction "PC12_80") (pintype "bidirectional"))
      (node (ref "X4") (pin "5") (pinfunction "SCLK_5") (pintype "passive"))
    )
    (net (code "91") (name "/SDIO_CMD") (class "Default")
      (node (ref "U1") (pin "83") (pinfunction "PD2_83") (pintype "bidirectional"))
      (node (ref "X4") (pin "3") (pinfunction "CMD_3") (pintype "passive"))
    )
    (net (code "92") (name "/SDIO_D0") (class "Default")
      (node (ref "U1") (pin "65") (pinfunction "PC8_65") (pintype "bidirectional"))
      (node (ref "X4") (pin "7") (pinfunction "D0_7") (pintype "passive"))
    )
    (net (code "93") (name "/SDIO_D1") (class "Default")
      (node (ref "U1") (pin "66") (pinfunction "PC9_66") (pintype "bidirectional"))
      (node (ref "X4") (pin "8") (pinfunction "D1_8") (pintype "passive"))
    )
    (net (code "94") (name "/SDIO_D2") (class "Default")
      (node (ref "U1") (pin "78") (pinfunction "PC10_78") (pintype "bidirectional"))
      (node (ref "X4") (pin "1") (pinfunction "D2_1") (pintype "passive"))
    )
    (net (code "95") (name "/SDIO_D3") (class "Default")
      (node (ref "U1") (pin "79") (pinfunction "PC11_79") (pintype "bidirectional"))
      (node (ref "X4") (pin "2") (pinfunction "D3_2") (pintype "passive"))
    )
    (net (code "96") (name "/SWCLK") (class "Default")
      (node (ref "U1") (pin "76") (pinfunction "PA14(JTCK-SWCLK)_76") (pintype "bidirectional"))
      (node (ref "X7") (pin "3") (pinfunction "3_3") (pintype "passive"))
    )
    (net (code "97") (name "/SWDIO") (class "Default")
      (node (ref "U1") (pin "72") (pinfunction "PA13(JTMS-SWDIO)_72") (pintype "bidirectional"))
      (node (ref "X7") (pin "2") (pinfunction "2_2") (pintype "passive"))
    )
    (net (code "98") (name "/SWO") (class "Default")
      (node (ref "U1") (pin "89") (pinfunction "PB3(JTDO/TRACESWO)_89") (pintype "bidirectional"))
      (node (ref "X7") (pin "4") (pinfunction "4_4") (pintype "passive"))
    )
    (net (code "99") (name "/Source_1") (class "Default")
      (node (ref "X8") (pin "2") (pinfunction "2_2") (pintype "passive"))
      (node (ref "XT1") (pin "10") (pinfunction "10_10") (pintype "passive"))
      (node (ref "XT1") (pin "2") (pinfunction "2_2") (pintype "passive"))
    )
    (net (code "100") (name "/Source_2") (class "Default")
      (node (ref "X9") (pin "2") (pinfunction "2_2") (pintype "passive"))
      (node (ref "XT1") (pin "15") (pinfunction "15_15") (pintype "passive"))
      (node (ref "XT1") (pin "22") (pinfunction "22_22") (pintype "passive"))
    )
    (net (code "101") (name "/USB_Case") (class "Default")
      (node (ref "L3") (pin "1") (pinfunction "1_1") (pintype "passive"))
      (node (ref "X2") (pin "0") (pinfunction "Shield_0") (pintype "passive"))
    )
    (net (code "102") (name "/USB_D+") (class "Default")
      (node (ref "D1") (pin "1") (pinfunction "cathode_1_1") (pintype "power_in"))
      (node (ref "L2") (pin "2") (pinfunction "2_2") (pintype "passive"))
      (node (ref "X2") (pin "3") (pinfunction "+D_3") (pintype "passive"))
    )
    (net (code "103") (name "/USB_D-") (class "Default")
      (node (ref "D2") (pin "1") (pinfunction "cathode_1_1") (pintype "power_in"))
      (node (ref "L2") (pin "1") (pinfunction "1_1") (pintype "passive"))
      (node (ref "X2") (pin "2") (pinfunction "-D_2") (pintype "passive"))
    )
    (net (code "104") (name "/U_subs") (class "Default")
      (node (ref "R20") (pin "1") (pinfunction "1_1") (pintype "passive"))
      (node (ref "U2") (pin "7") (pinfunction "OUT_B_7") (pintype "output"))
      (node (ref "XT1") (pin "16") (pinfunction "16_16") (pintype "passive"))
      (node (ref "XT1") (pin "21") (pinfunction "21_21") (pintype "passive"))
    )
    (net (code "105") (name "/V_CURR_0") (class "Default")
      (node (ref "X1") (pin "1") (pinfunction "1_1") (pintype "passive"))
      (node (ref "X1") (pin "2") (pinfunction "2_2") (pintype "passive"))
    )
    (net (code "106") (name "/V_CURR_1") (class "Default")
      (node (ref "X3") (pin "1") (pinfunction "1_1") (pintype "passive"))
      (node (ref "X3") (pin "2") (pinfunction "2_2") (pintype "passive"))
    )
    (net (code "107") (name "/V_CURR_2") (class "Default")
      (node (ref "X5") (pin "1") (pinfunction "1_1") (pintype "passive"))
      (node (ref "X5") (pin "2") (pinfunction "2_2") (pintype "passive"))
    )
    (net (code "108") (name "/V_CURR_3") (class "Default")
      (node (ref "X6") (pin "1") (pinfunction "1_1") (pintype "passive"))
      (node (ref "X6") (pin "2") (pinfunction "2_2") (pintype "passive"))
    )
    (net (code "113") (name "GND") (class "Default")
      (node (ref "C17") (pin "2") (pinfunction "2_2") (pintype "passive"))
      (node (ref "C18") (pin "1") (pinfunction "1_1") (pintype "passive"))
      (node (ref "C19") (pin "1") (pinfunction "1_1") (pintype "passive"))
      (node (ref "C20") (pin "1") (pinfunction "1_1") (pintype "passive"))
      (node (ref "C21") (pin "1") (pinfunction "1_1") (pintype "passive"))
      (node (ref "C22") (pin "1") (pinfunction "1_1") (pintype "passive"))
      (node (ref "C23") (pin "1") (pinfunction "1_1") (pintype "passive"))
      (node (ref "C24") (pin "1") (pinfunction "1_1") (pintype "passive"))
      (node (ref "C25") (pin "1") (pinfunction "1_1") (pintype "passive"))
      (node (ref "C26") (pin "1") (pinfunction "1_1") (pintype "passive"))
      (node (ref "C27") (pin "1") (pinfunction "1_1") (pintype "passive"))
      (node (ref "C28") (pin "1") (pinfunction "1_1") (pintype "passive"))
      (node (ref "C29") (pin "1") (pinfunction "1_1") (pintype "passive"))
      (node (ref "C31") (pin "1") (pinfunction "1_1") (pintype "passive"))
      (node (ref "C32") (pin "1") (pinfunction "1_1") (pintype "passive"))
      (node (ref "C33") (pin "1") (pinfunction "1_1") (pintype "passive"))
      (node (ref "C34") (pin "1") (pinfunction "1_1") (pintype "passive"))
      (node (ref "C35") (pin "1") (pinfunction "1_1") (pintype "passive"))
      (node (ref "C36") (pin "1") (pinfunction "1_1") (pintype "passive"))
      (node (ref "C37") (pin "1") (pinfunction "1_1") (pintype "passive"))
      (node (ref "C38") (pin "1") (pinfunction "1_1") (pintype "passive"))
      (node (ref "C39") (pin "1") (pinfunction "1_1") (pintype "passive"))
      (node (ref "C61") (pin "1") (pinfunction "1_1") (pintype "passive"))
      (node (ref "C62") (pin "1") (pinfunction "1_1") (pintype "passive"))
      (node (ref "D1") (pin "2") (pinfunction "cathode_2_2") (pintype "power_in"))
      (node (ref "D2") (pin "2") (pinfunction "cathode_2_2") (pintype "power_in"))
      (node (ref "D3") (pin "2") (pinfunction "K_2") (pintype "passive"))
      (node (ref "D4") (pin "2") (pinfunction "K_2") (pintype "passive"))
      (node (ref "D5") (pin "2") (pinfunction "K_2") (pintype "passive"))
      (node (ref "GK1") (pin "2") (pinfunction "GND_2") (pintype "passive"))
      (node (ref "L3") (pin "2") (pinfunction "2_2") (pintype "passive"))
      (node (ref "L5") (pin "2") (pinfunction "2_2") (pintype "passive"))
      (node (ref "R19") (pin "2") (pinfunction "2_2") (pintype "passive"))
      (node (ref "R23") (pin "1") (pinfunction "1_1") (pintype "passive"))
      (node (ref "R25") (pin "2") (pinfunction "2_2") (pintype "passive"))
      (node (ref "R40") (pin "1") (pinfunction "1_1") (pintype "passive"))
      (node (ref "R44") (pin "2") (pinfunction "2_2") (pintype "passive"))
      (node (ref "U1") (pin "10") (pinfunction "VSS_10") (pintype "power_in"))
      (node (ref "U1") (pin "13") (pinfunction "PH1-OSC_OUT(PH1)_13") (pintype "bidirectional"))
      (node (ref "U1") (pin "27") (pinfunction "VSS_27") (pintype "power_in"))
      (node (ref "U1") (pin "74") (pinfunction "VSS_74") (pintype "power_in"))
      (node (ref "U1") (pin "99") (pinfunction "VSS_99") (pintype "power_in"))
      (node (ref "X1") (pin "25") (pinfunction "25_25") (pintype "passive"))
      (node (ref "X1") (pin "26") (pinfunction "26_26") (pintype "passive"))
      (node (ref "X2") (pin "5") (pinfunction "GND_5") (pintype "passive"))
      (node (ref "X3") (pin "25") (pinfunction "25_25") (pintype "passive"))
      (node (ref "X3") (pin "26") (pinfunction "26_26") (pintype "passive"))
      (node (ref "X4") (pin "6") (pinfunction "GND_6") (pintype "passive"))
      (node (ref "X4") (pin "Gd") (pinfunction "Guard_Gd") (pintype "passive"))
      (node (ref "X4") (pin "MP0") (pinfunction "MPad_MP0") (pintype "passive"))
      (node (ref "X5") (pin "25") (pinfunction "25_25") (pintype "passive"))
      (node (ref "X5") (pin "26") (pinfunction "26_26") (pintype "passive"))
      (node (ref "X6") (pin "25") (pinfunction "25_25") (pintype "passive"))
      (node (ref "X6") (pin "26") (pinfunction "26_26") (pintype "passive"))
      (node (ref "X7") (pin "1") (pinfunction "1_1") (pintype "passive"))
      (node (ref "X8") (pin "3") (pinfunction "3_3") (pintype "passive"))
      (node (ref "X9") (pin "3") (pinfunction "3_3") (pintype "passive"))
    )
    (net (code "114") (name "GND_A") (class "Default")
      (node (ref "C30") (pin "1") (pinfunction "1_1") (pintype "passive"))
      (node (ref "C40") (pin "1") (pinfunction "1_1") (pintype "passive"))
      (node (ref "C41") (pin "1") (pinfunction "1_1") (pintype "passive"))
      (node (ref "L5") (pin "1") (pinfunction "1_1") (pintype "passive"))
      (node (ref "U1") (pin "20") (pinfunction "VSSA_20") (pintype "power_in"))
      (node (ref "X1") (pin "3") (pinfunction "3_3") (pintype "passive"))
      (node (ref "X1") (pin "4") (pinfunction "4_4") (pintype "passive"))
      (node (ref "X3") (pin "3") (pinfunction "3_3") (pintype "passive"))
      (node (ref "X3") (pin "4") (pinfunction "4_4") (pintype "passive"))
      (node (ref "X5") (pin "3") (pinfunction "3_3") (pintype "passive"))
      (node (ref "X5") (pin "4") (pinfunction "4_4") (pintype "passive"))
      (node (ref "X6") (pin "3") (pinfunction "3_3") (pintype "passive"))
      (node (ref "X6") (pin "4") (pinfunction "4_4") (pintype "passive"))
    )
    (net (code "115") (name "Net-(D3-A)") (class "Default")
      (node (ref "D3") (pin "1") (pinfunction "A_1") (pintype "passive"))
      (node (ref "R36") (pin "2") (pinfunction "2_2") (pintype "passive"))
    )
    (net (code "116") (name "Net-(D4-A)") (class "Default")
      (node (ref "D4") (pin "1") (pinfunction "A_1") (pintype "passive"))
      (node (ref "R37") (pin "2") (pinfunction "2_2") (pintype "passive"))
    )
    (net (code "117") (name "Net-(D5-A)") (class "Default")
      (node (ref "D5") (pin "1") (pinfunction "A_1") (pintype "passive"))
      (node (ref "R38") (pin "2") (pinfunction "2_2") (pintype "passive"))
    )
    (net (code "118") (name "Net-(L2-Pad3)") (class "Default")
      (node (ref "L2") (pin "3") (pinfunction "3_3") (pintype "passive"))
      (node (ref "R17") (pin "2") (pinfunction "2_2") (pintype "passive"))
    )
    (net (code "119") (name "Net-(L2-Pad4)") (class "Default")
      (node (ref "L2") (pin "4") (pinfunction "4_4") (pintype "passive"))
      (node (ref "R18") (pin "2") (pinfunction "2_2") (pintype "passive"))
    )
    (net (code "120") (name "Net-(R40-Pad2)") (class "Default")
      (node (ref "R40") (pin "2") (pinfunction "2_2") (pintype "passive"))
      (node (ref "SW1") (pin "1") (pinfunction "1_1") (pintype "passive"))
    )
    (net (code "121") (name "Net-(U1A-BOOT0)") (class "Default")
      (node (ref "R23") (pin "2") (pinfunction "2_2") (pintype "passive"))
      (node (ref "U1") (pin "94") (pinfunction "BOOT0_94") (pintype "input"))
    )
    (net (code "122") (name "Net-(U1A-PH0-OSC_IN(PH0))") (class "Default")
      (node (ref "R21") (pin "1") (pinfunction "1_1") (pintype "passive"))
      (node (ref "U1") (pin "12") (pinfunction "PH0-OSC_IN(PH0)_12") (pintype "bidirectional"))
    )
    (net (code "123") (name "Net-(U1A-VCAP_1)") (class "Default")
      (node (ref "C24") (pin "2") (pinfunction "2_2") (pintype "passive"))
      (node (ref "U1") (pin "49") (pinfunction "VCAP_1_49") (pintype "power_in"))
    )
    (net (code "124") (name "Net-(U1A-VCAP_2)") (class "Default")
      (node (ref "C23") (pin "2") (pinfunction "2_2") (pintype "passive"))
      (node (ref "U1") (pin "73") (pinfunction "VCAP_2_73") (pintype "power_in"))
    )
    (net (code "125") (name "Net-(U2A-+IN_A)") (class "Default")
      (node (ref "R25") (pin "1") (pinfunction "1_1") (pintype "passive"))
      (node (ref "U2") (pin "3") (pinfunction "+IN_A_3") (pintype "input"))
    )
    (net (code "126") (name "Net-(U2A--IN_A)") (class "Default")
      (node (ref "R22") (pin "2") (pinfunction "2_2") (pintype "passive"))
      (node (ref "R24") (pin "1") (pinfunction "1_1") (pintype "passive"))
      (node (ref "U2") (pin "2") (pinfunction "-IN_A_2") (pintype "input"))
    )
    (net (code "127") (name "Net-(U2B--IN_B)") (class "Default")
      (node (ref "R19") (pin "1") (pinfunction "1_1") (pintype "passive"))
      (node (ref "R20") (pin "2") (pinfunction "2_2") (pintype "passive"))
      (node (ref "U2") (pin "6") (pinfunction "-IN_B_6") (pintype "input"))
    )
    (net (code "128") (name "Net-(X2-VBus)") (class "Default")
      (node (ref "C19") (pin "2") (pinfunction "2_2") (pintype "passive"))
      (node (ref "L1") (pin "1") (pinfunction "1_1") (pintype "passive"))
      (node (ref "X2") (pin "1") (pinfunction "VBus_1") (pintype "passive"))
    )
    (net (code "129") (name "USB_+5V") (class "Default")
      (node (ref "C17") (pin "1") (pinfunction "1_1") (pintype "passive"))
      (node (ref "C20") (pin "2") (pinfunction "2_2") (pintype "passive"))
      (node (ref "L1") (pin "2") (pinfunction "2_2") (pintype "passive"))
    )
    (net (code "130") (name "unconnected-(U1A-PA8-Pad67)") (class "Default")
      (node (ref "U1") (pin "67") (pinfunction "PA8_67") (pintype "bidirectional"))
    )
    (net (code "131") (name "unconnected-(U1A-PA9-Pad68)") (class "Default")
      (node (ref "U1") (pin "68") (pinfunction "PA9_68") (pintype "bidirectional"))
    )
    (net (code "132") (name "unconnected-(U1A-PA10-Pad69)") (class "Default")
      (node (ref "U1") (pin "69") (pinfunction "PA10_69") (pintype "bidirectional"))
    )
    (net (code "133") (name "unconnected-(U1A-PA15(JTDI)-Pad77)") (class "Default")
      (node (ref "U1") (pin "77") (pinfunction "PA15(JTDI)_77") (pintype "bidirectional"))
    )
    (net (code "134") (name "unconnected-(U1A-PB2-BOOT1(PB2)-Pad37)") (class "Default")
      (node (ref "U1") (pin "37") (pinfunction "PB2-BOOT1(PB2)_37") (pintype "bidirectional"))
    )
    (net (code "135") (name "unconnected-(U1A-PB4(NJTRST)-Pad90)") (class "Default")
      (node (ref "U1") (pin "90") (pinfunction "PB4(NJTRST)_90") (pintype "bidirectional"))
    )
    (net (code "136") (name "unconnected-(U1A-PB5-Pad91)") (class "Default")
      (node (ref "U1") (pin "91") (pinfunction "PB5_91") (pintype "bidirectional"))
    )
    (net (code "137") (name "unconnected-(U1A-PB8-Pad95)") (class "Default")
      (node (ref "U1") (pin "95") (pinfunction "PB8_95") (pintype "bidirectional"))
    )
    (net (code "138") (name "unconnected-(U1A-PB9-Pad96)") (class "Default")
      (node (ref "U1") (pin "96") (pinfunction "PB9_96") (pintype "bidirectional"))
    )
    (net (code "139") (name "unconnected-(U1A-PC6-Pad63)") (class "Default")
      (node (ref "U1") (pin "63") (pinfunction "PC6_63") (pintype "bidirectional"))
    )
    (net (code "140") (name "unconnected-(U1A-PC7-Pad64)") (class "Default")
      (node (ref "U1") (pin "64") (pinfunction "PC7_64") (pintype "bidirectional"))
    )
    (net (code "141") (name "unconnected-(U1A-PC13-Pad7)") (class "Default")
      (node (ref "U1") (pin "7") (pinfunction "PC13_7") (pintype "bidirectional"))
    )
    (net (code "142") (name "unconnected-(U1A-PC14-OSC32_IN(PC14)-Pad8)") (class "Default")
      (node (ref "U1") (pin "8") (pinfunction "PC14-OSC32_IN(PC14)_8") (pintype "bidirectional"))
    )
    (net (code "143") (name "unconnected-(U1A-PC15-OSC32_OUT(PC15)-Pad9)") (class "Default")
      (node (ref "U1") (pin "9") (pinfunction "PC15-OSC32_OUT(PC15)_9") (pintype "bidirectional"))
    )
    (net (code "144") (name "unconnected-(U1A-PD0-Pad81)") (class "Default")
      (node (ref "U1") (pin "81") (pinfunction "PD0_81") (pintype "bidirectional"))
    )
    (net (code "145") (name "unconnected-(U1A-PD1-Pad82)") (class "Default")
      (node (ref "U1") (pin "82") (pinfunction "PD1_82") (pintype "bidirectional"))
    )
    (net (code "146") (name "unconnected-(U1A-PD3-Pad84)") (class "Default")
      (node (ref "U1") (pin "84") (pinfunction "PD3_84") (pintype "bidirectional"))
    )
    (net (code "147") (name "unconnected-(U1A-PD4-Pad85)") (class "Default")
      (node (ref "U1") (pin "85") (pinfunction "PD4_85") (pintype "bidirectional"))
    )
    (net (code "148") (name "unconnected-(U1A-PD5-Pad86)") (class "Default")
      (node (ref "U1") (pin "86") (pinfunction "PD5_86") (pintype "bidirectional"))
    )
    (net (code "149") (name "unconnected-(U1A-PD6-Pad87)") (class "Default")
      (node (ref "U1") (pin "87") (pinfunction "PD6_87") (pintype "bidirectional"))
    )
    (net (code "150") (name "unconnected-(U1A-PD7-Pad88)") (class "Default")
      (node (ref "U1") (pin "88") (pinfunction "PD7_88") (pintype "bidirectional"))
    )
    (net (code "151") (name "unconnected-(X2-ID-Pad4)") (class "Default")
      (node (ref "X2") (pin "4") (pinfunction "ID_4") (pintype "passive"))
    )
    (net (code "152") (name "unconnected-(XT1-Pad9)") (class "Default")
      (node (ref "XT1") (pin "9") (pinfunction "9_9") (pintype "passive"))
    )
  )
)
